# Sheet1.net
KiCad netlist of a schematic drawn in Altium Designer
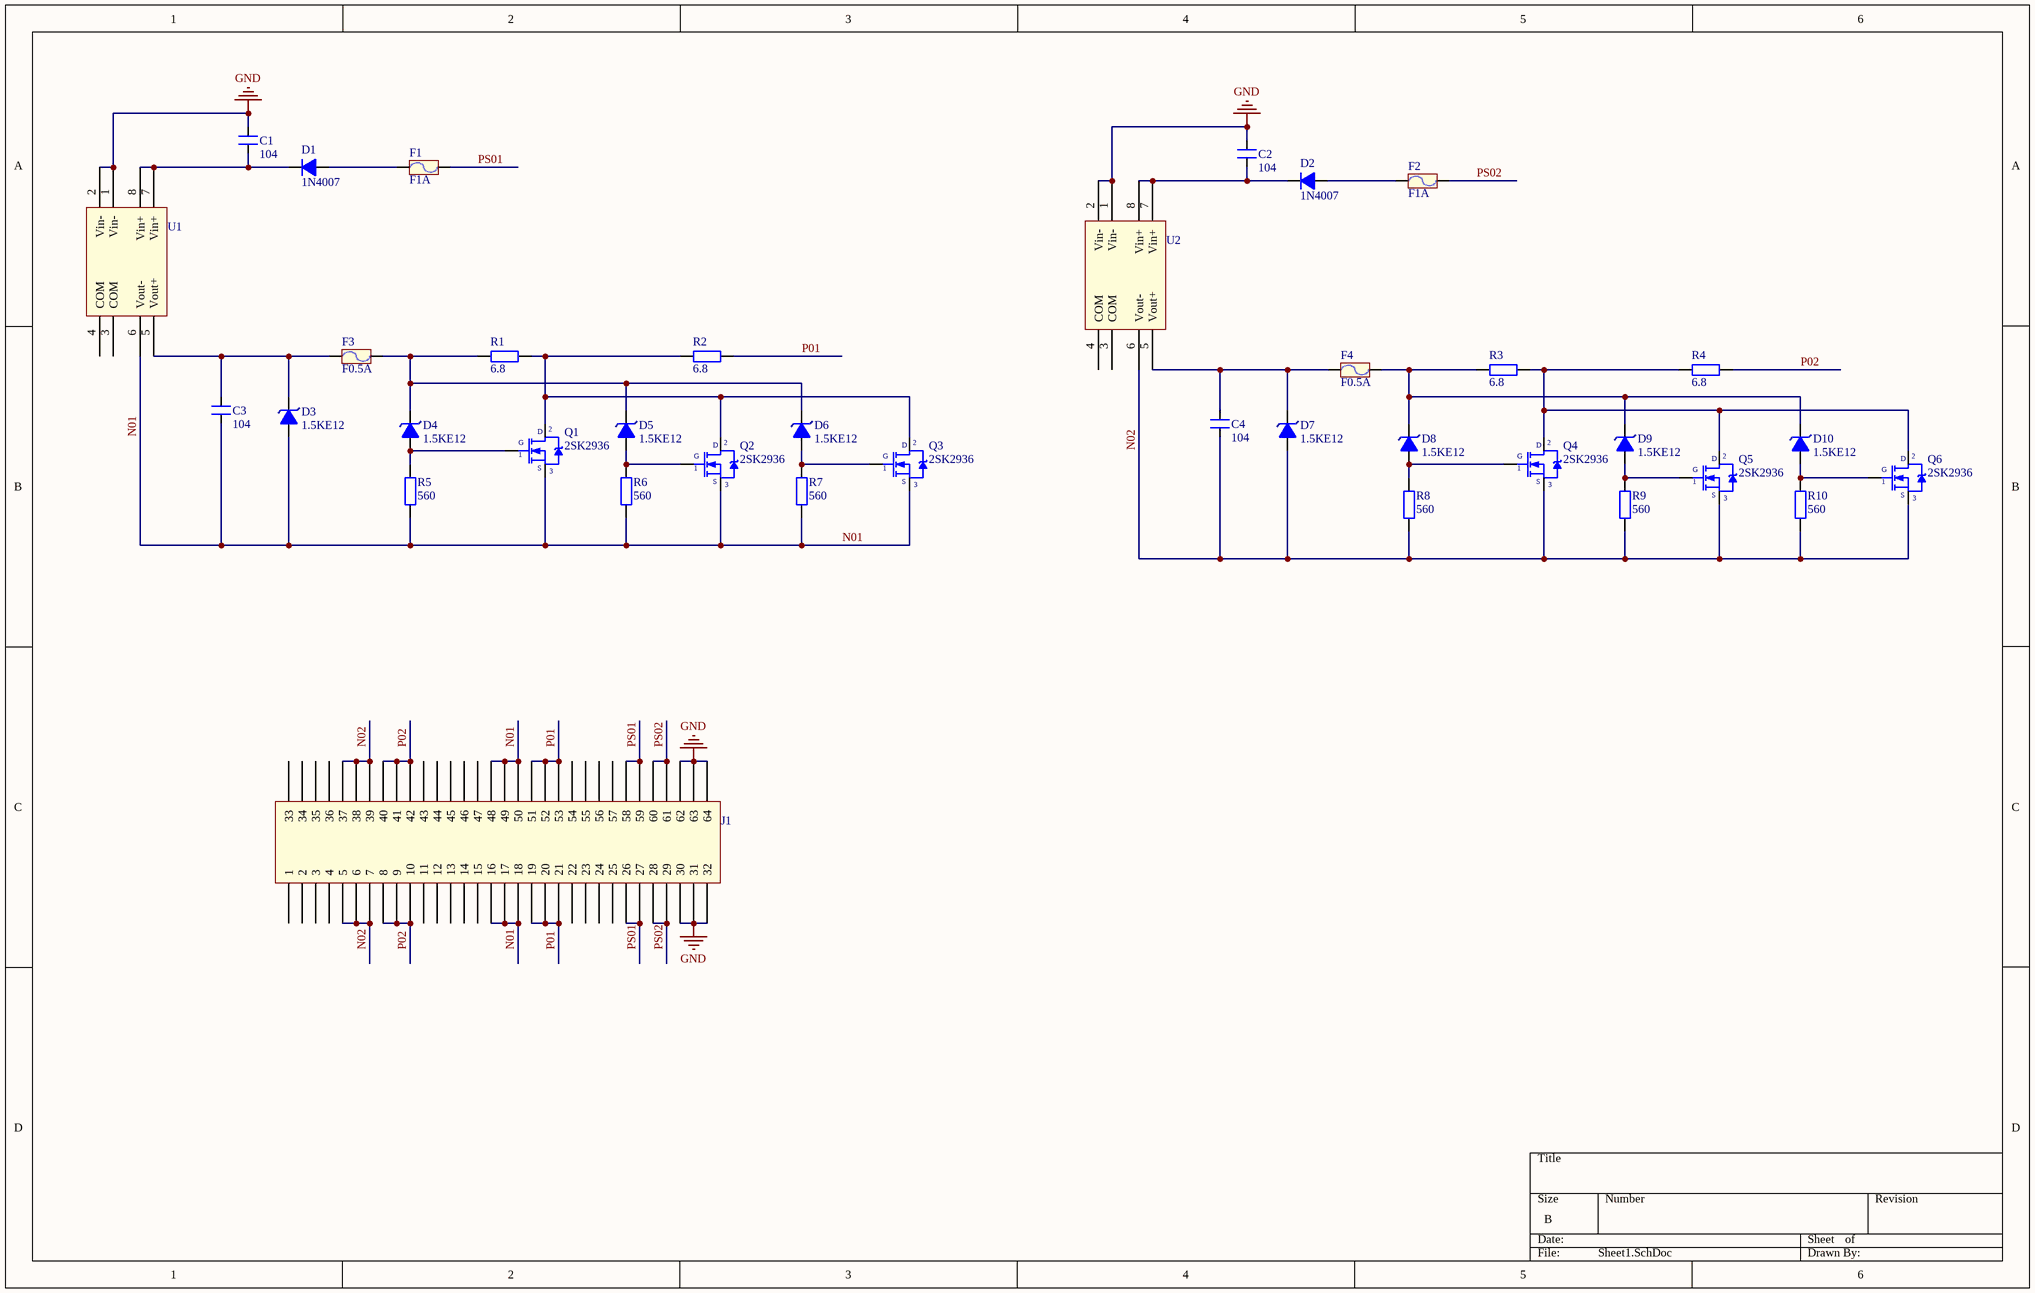
[diagram p0: Sheet1.SchDoc]

(export (version "E")
  (design (tool "Eeschema 10.0.6"))
  (components
    (comp (ref "C1")
      (value "104")
      (footprint "CN1")
      (description "Cremic For Xtal 1pF => 100pF")
      (libsource (lib "Binh_BK") (part "CAP"))
    )
    (comp (ref "C2")
      (value "104")
      (footprint "CN1")
      (description "Cremic For Xtal 1pF => 100pF")
      (libsource (lib "Binh_BK") (part "CAP"))
    )
    (comp (ref "C3")
      (value "104")
      (footprint "CN1")
      (description "Cremic For Xtal 1pF => 100pF")
      (libsource (lib "Binh_BK") (part "CAP"))
    )
    (comp (ref "C4")
      (value "104")
      (footprint "CN1")
      (description "Cremic For Xtal 1pF => 100pF")
      (libsource (lib "Binh_BK") (part "CAP"))
    )
    (comp (ref "D1")
      (value "1N4007")
      (footprint "D1A")
      (description "Diode 1A")
      (libsource (lib "Binh_BK") (part "D1A"))
    )
    (comp (ref "D2")
      (value "1N4007")
      (footprint "D1A")
      (description "Diode 1A")
      (libsource (lib "Binh_BK") (part "D1A"))
    )
    (comp (ref "D3") (value "1.5KE12") (footprint "D1A") (libsource (lib "Binh_BK") (part "Zener")))
    (comp (ref "D4") (value "1.5KE12") (footprint "D1A") (libsource (lib "Binh_BK") (part "Zener")))
    (comp (ref "D5") (value "1.5KE12") (footprint "D1A") (libsource (lib "Binh_BK") (part "Zener")))
    (comp (ref "D6") (value "1.5KE12") (footprint "D1A") (libsource (lib "Binh_BK") (part "Zener")))
    (comp (ref "D7") (value "1.5KE12") (footprint "D1A") (libsource (lib "Binh_BK") (part "Zener")))
    (comp (ref "D8") (value "1.5KE12") (footprint "D1A") (libsource (lib "Binh_BK") (part "Zener")))
    (comp (ref "D9") (value "1.5KE12") (footprint "D1A") (libsource (lib "Binh_BK") (part "Zener")))
    (comp (ref "D10") (value "1.5KE12") (footprint "D1A") (libsource (lib "Binh_BK") (part "Zener")))
    (comp (ref "F1")
      (value "F1A")
      (footprint "Fuse")
      (description "Fuse")
      (fields (field (name "DESIGNED BY") "VanDungEvn"))
      (libsource (lib "") (part "Fuse_1"))
    )
    (comp (ref "F2")
      (value "F1A")
      (footprint "Fuse")
      (description "Fuse")
      (fields (field (name "DESIGNED BY") "VanDungEvn"))
      (libsource (lib "") (part "Fuse_1"))
    )
    (comp (ref "F3")
      (value "F0.5A")
      (footprint "Fuse")
      (description "Fuse")
      (fields (field (name "DESIGNED BY") "VanDungEvn"))
      (libsource (lib "Binh_BK") (part "Fuse"))
    )
    (comp (ref "F4")
      (value "F0.5A")
      (footprint "Fuse")
      (description "Fuse")
      (fields (field (name "DESIGNED BY") "VanDungEvn"))
      (libsource (lib "Binh_BK") (part "Fuse"))
    )
    (comp (ref "J1")
      (value "Header 32x2")
      (footprint "Header32x2")
      (libsource (lib "dung_maker_2018") (part "Header 32x2"))
    )
    (comp (ref "Q1")
      (value "2SK2936")
      (footprint "QTO-220")
      (description "MOSFET N - CHANNEL 500V - 0.75 - 8A - TO-220")
      (libsource (lib "Binh_BK") (part "IRF840"))
    )
    (comp (ref "Q2")
      (value "2SK2936")
      (footprint "QTO-220")
      (description "MOSFET N - CHANNEL 500V - 0.75 - 8A - TO-220")
      (libsource (lib "Binh_BK") (part "IRF840"))
    )
    (comp (ref "Q3")
      (value "2SK2936")
      (footprint "QTO-220")
      (description "MOSFET N - CHANNEL 500V - 0.75 - 8A - TO-220")
      (libsource (lib "Binh_BK") (part "IRF840"))
    )
    (comp (ref "Q4")
      (value "2SK2936")
      (footprint "QTO-220")
      (description "MOSFET N - CHANNEL 500V - 0.75 - 8A - TO-220")
      (libsource (lib "Binh_BK") (part "IRF840"))
    )
    (comp (ref "Q5")
      (value "2SK2936")
      (footprint "QTO-220")
      (description "MOSFET N - CHANNEL 500V - 0.75 - 8A - TO-220")
      (libsource (lib "Binh_BK") (part "IRF840"))
    )
    (comp (ref "Q6")
      (value "2SK2936")
      (footprint "QTO-220")
      (description "MOSFET N - CHANNEL 500V - 0.75 - 8A - TO-220")
      (libsource (lib "Binh_BK") (part "IRF840"))
    )
    (comp (ref "R1")
      (value "6.8")
      (footprint "R5W")
      (description "Resistor 1/4W")
      (libsource (lib "Binh_BK") (part "R1/4W"))
    )
    (comp (ref "R2")
      (value "6.8")
      (footprint "R5W")
      (description "Resistor 1/4W")
      (libsource (lib "Binh_BK") (part "R1/4W"))
    )
    (comp (ref "R3")
      (value "6.8")
      (footprint "R5W")
      (description "Resistor 1/4W")
      (libsource (lib "Binh_BK") (part "R1/4W"))
    )
    (comp (ref "R4")
      (value "6.8")
      (footprint "R5W")
      (description "Resistor 1/4W")
      (libsource (lib "Binh_BK") (part "R1/4W"))
    )
    (comp (ref "R5")
      (value "560")
      (footprint "R1/4W")
      (description "Resistor 1/4W")
      (libsource (lib "Binh_BK") (part "R1/4W"))
    )
    (comp (ref "R6")
      (value "560")
      (footprint "R1/4W")
      (description "Resistor 1/4W")
      (libsource (lib "Binh_BK") (part "R1/4W"))
    )
    (comp (ref "R7")
      (value "560")
      (footprint "R1/4W")
      (description "Resistor 1/4W")
      (libsource (lib "Binh_BK") (part "R1/4W"))
    )
    (comp (ref "R8")
      (value "560")
      (footprint "R1/4W")
      (description "Resistor 1/4W")
      (libsource (lib "Binh_BK") (part "R1/4W"))
    )
    (comp (ref "R9")
      (value "560")
      (footprint "R1/4W")
      (description "Resistor 1/4W")
      (libsource (lib "Binh_BK") (part "R1/4W"))
    )
    (comp (ref "R10")
      (value "560")
      (footprint "R1/4W")
      (description "Resistor 1/4W")
      (libsource (lib "Binh_BK") (part "R1/4W"))
    )
    (comp (ref "U1") (value "ASA01xx") (footprint "ASA") (libsource (lib "dung_maker_2018") (part "ASA01")))
    (comp (ref "U2") (value "ASA01xx") (footprint "ASA") (libsource (lib "dung_maker_2018") (part "ASA01")))
  )
  (nets
    (net (code "1") (name "/N01") (class "Default")
      (node (ref "C3") (pin "1") (pinfunction "1_1") (pintype "passive"))
      (node (ref "D3") (pin "1") (pinfunction "A_1") (pintype "passive"))
      (node (ref "J1") (pin "16") (pinfunction "16_16") (pintype "passive"))
      (node (ref "J1") (pin "17") (pinfunction "17_17") (pintype "passive"))
      (node (ref "J1") (pin "18") (pinfunction "18_18") (pintype "passive"))
      (node (ref "J1") (pin "48") (pinfunction "48_48") (pintype "passive"))
      (node (ref "J1") (pin "49") (pinfunction "49_49") (pintype "passive"))
      (node (ref "J1") (pin "50") (pinfunction "50_50") (pintype "passive"))
      (node (ref "Q1") (pin "3") (pinfunction "S_3") (pintype "passive"))
      (node (ref "Q2") (pin "3") (pinfunction "S_3") (pintype "passive"))
      (node (ref "Q3") (pin "3") (pinfunction "S_3") (pintype "passive"))
      (node (ref "R5") (pin "1") (pinfunction "1_1") (pintype "passive"))
      (node (ref "R6") (pin "1") (pinfunction "1_1") (pintype "passive"))
      (node (ref "R7") (pin "1") (pinfunction "1_1") (pintype "passive"))
      (node (ref "U1") (pin "6") (pinfunction "Vout-_6") (pintype "passive"))
    )
    (net (code "2") (name "/N02") (class "Default")
      (node (ref "C4") (pin "1") (pinfunction "1_1") (pintype "passive"))
      (node (ref "D7") (pin "1") (pinfunction "A_1") (pintype "passive"))
      (node (ref "J1") (pin "37") (pinfunction "37_37") (pintype "passive"))
      (node (ref "J1") (pin "38") (pinfunction "38_38") (pintype "passive"))
      (node (ref "J1") (pin "39") (pinfunction "39_39") (pintype "passive"))
      (node (ref "J1") (pin "5") (pinfunction "5_5") (pintype "passive"))
      (node (ref "J1") (pin "6") (pinfunction "6_6") (pintype "passive"))
      (node (ref "J1") (pin "7") (pinfunction "7_7") (pintype "passive"))
      (node (ref "Q4") (pin "3") (pinfunction "S_3") (pintype "passive"))
      (node (ref "Q5") (pin "3") (pinfunction "S_3") (pintype "passive"))
      (node (ref "Q6") (pin "3") (pinfunction "S_3") (pintype "passive"))
      (node (ref "R10") (pin "1") (pinfunction "1_1") (pintype "passive"))
      (node (ref "R8") (pin "1") (pinfunction "1_1") (pintype "passive"))
      (node (ref "R9") (pin "1") (pinfunction "1_1") (pintype "passive"))
      (node (ref "U2") (pin "6") (pinfunction "Vout-_6") (pintype "passive"))
    )
    (net (code "3") (name "/P01") (class "Default")
      (node (ref "J1") (pin "19") (pinfunction "19_19") (pintype "passive"))
      (node (ref "J1") (pin "20") (pinfunction "20_20") (pintype "passive"))
      (node (ref "J1") (pin "21") (pinfunction "21_21") (pintype "passive"))
      (node (ref "J1") (pin "51") (pinfunction "51_51") (pintype "passive"))
      (node (ref "J1") (pin "52") (pinfunction "52_52") (pintype "passive"))
      (node (ref "J1") (pin "53") (pinfunction "53_53") (pintype "passive"))
      (node (ref "R2") (pin "1") (pinfunction "1_1") (pintype "passive"))
    )
    (net (code "4") (name "/P02") (class "Default")
      (node (ref "J1") (pin "10") (pinfunction "10_10") (pintype "passive"))
      (node (ref "J1") (pin "40") (pinfunction "40_40") (pintype "passive"))
      (node (ref "J1") (pin "41") (pinfunction "41_41") (pintype "passive"))
      (node (ref "J1") (pin "42") (pinfunction "42_42") (pintype "passive"))
      (node (ref "J1") (pin "8") (pinfunction "8_8") (pintype "passive"))
      (node (ref "J1") (pin "9") (pinfunction "9_9") (pintype "passive"))
      (node (ref "R4") (pin "1") (pinfunction "1_1") (pintype "passive"))
    )
    (net (code "5") (name "/PS01") (class "Default")
      (node (ref "F1") (pin "2") (pinfunction "2_2") (pintype "passive"))
      (node (ref "J1") (pin "26") (pinfunction "26_26") (pintype "passive"))
      (node (ref "J1") (pin "27") (pinfunction "27_27") (pintype "passive"))
      (node (ref "J1") (pin "58") (pinfunction "58_58") (pintype "passive"))
      (node (ref "J1") (pin "59") (pinfunction "59_59") (pintype "passive"))
    )
    (net (code "6") (name "/PS02") (class "Default")
      (node (ref "F2") (pin "2") (pinfunction "2_2") (pintype "passive"))
      (node (ref "J1") (pin "28") (pinfunction "28_28") (pintype "passive"))
      (node (ref "J1") (pin "29") (pinfunction "29_29") (pintype "passive"))
      (node (ref "J1") (pin "60") (pinfunction "60_60") (pintype "passive"))
      (node (ref "J1") (pin "61") (pinfunction "61_61") (pintype "passive"))
    )
    (net (code "7") (name "GND") (class "Default")
      (node (ref "C1") (pin "2") (pinfunction "2_2") (pintype "passive"))
      (node (ref "C2") (pin "2") (pinfunction "2_2") (pintype "passive"))
      (node (ref "J1") (pin "30") (pinfunction "30_30") (pintype "passive"))
      (node (ref "J1") (pin "31") (pinfunction "31_31") (pintype "passive"))
      (node (ref "J1") (pin "32") (pinfunction "32_32") (pintype "passive"))
      (node (ref "J1") (pin "62") (pinfunction "62_62") (pintype "passive"))
      (node (ref "J1") (pin "63") (pinfunction "63_63") (pintype "passive"))
      (node (ref "J1") (pin "64") (pinfunction "64_64") (pintype "passive"))
      (node (ref "U1") (pin "1") (pinfunction "Vin-_1") (pintype "passive"))
      (node (ref "U1") (pin "2") (pinfunction "Vin-_2") (pintype "passive"))
      (node (ref "U2") (pin "1") (pinfunction "Vin-_1") (pintype "passive"))
      (node (ref "U2") (pin "2") (pinfunction "Vin-_2") (pintype "passive"))
    )
    (net (code "8") (name "Net-(D1-A)") (class "Default")
      (node (ref "D1") (pin "1") (pinfunction "A_1") (pintype "passive"))
      (node (ref "F1") (pin "1") (pinfunction "1_1") (pintype "passive"))
    )
    (net (code "9") (name "Net-(D1-K)") (class "Default")
      (node (ref "C1") (pin "1") (pinfunction "1_1") (pintype "passive"))
      (node (ref "D1") (pin "2") (pinfunction "K_2") (pintype "passive"))
      (node (ref "U1") (pin "7") (pinfunction "Vin+_7") (pintype "passive"))
      (node (ref "U1") (pin "8") (pinfunction "Vin+_8") (pintype "passive"))
    )
    (net (code "10") (name "Net-(D2-A)") (class "Default")
      (node (ref "D2") (pin "1") (pinfunction "A_1") (pintype "passive"))
      (node (ref "F2") (pin "1") (pinfunction "1_1") (pintype "passive"))
    )
    (net (code "11") (name "Net-(D2-K)") (class "Default")
      (node (ref "C2") (pin "1") (pinfunction "1_1") (pintype "passive"))
      (node (ref "D2") (pin "2") (pinfunction "K_2") (pintype "passive"))
      (node (ref "U2") (pin "7") (pinfunction "Vin+_7") (pintype "passive"))
      (node (ref "U2") (pin "8") (pinfunction "Vin+_8") (pintype "passive"))
    )
    (net (code "12") (name "Net-(D3-K)") (class "Default")
      (node (ref "C3") (pin "2") (pinfunction "2_2") (pintype "passive"))
      (node (ref "D3") (pin "2") (pinfunction "K_2") (pintype "passive"))
      (node (ref "F3") (pin "2") (pinfunction "2_2") (pintype "passive"))
      (node (ref "U1") (pin "5") (pinfunction "Vout+_5") (pintype "passive"))
    )
    (net (code "13") (name "Net-(D4-A)") (class "Default")
      (node (ref "D4") (pin "1") (pinfunction "A_1") (pintype "passive"))
      (node (ref "Q1") (pin "1") (pinfunction "G_1") (pintype "passive"))
      (node (ref "R5") (pin "2") (pinfunction "2_2") (pintype "passive"))
    )
    (net (code "14") (name "Net-(D4-K)") (class "Default")
      (node (ref "D4") (pin "2") (pinfunction "K_2") (pintype "passive"))
      (node (ref "D5") (pin "2") (pinfunction "K_2") (pintype "passive"))
      (node (ref "D6") (pin "2") (pinfunction "K_2") (pintype "passive"))
      (node (ref "F3") (pin "1") (pinfunction "1_1") (pintype "passive"))
      (node (ref "R1") (pin "2") (pinfunction "2_2") (pintype "passive"))
    )
    (net (code "15") (name "Net-(D5-A)") (class "Default")
      (node (ref "D5") (pin "1") (pinfunction "A_1") (pintype "passive"))
      (node (ref "Q2") (pin "1") (pinfunction "G_1") (pintype "passive"))
      (node (ref "R6") (pin "2") (pinfunction "2_2") (pintype "passive"))
    )
    (net (code "16") (name "Net-(D6-A)") (class "Default")
      (node (ref "D6") (pin "1") (pinfunction "A_1") (pintype "passive"))
      (node (ref "Q3") (pin "1") (pinfunction "G_1") (pintype "passive"))
      (node (ref "R7") (pin "2") (pinfunction "2_2") (pintype "passive"))
    )
    (net (code "17") (name "Net-(D7-K)") (class "Default")
      (node (ref "C4") (pin "2") (pinfunction "2_2") (pintype "passive"))
      (node (ref "D7") (pin "2") (pinfunction "K_2") (pintype "passive"))
      (node (ref "F4") (pin "2") (pinfunction "2_2") (pintype "passive"))
      (node (ref "U2") (pin "5") (pinfunction "Vout+_5") (pintype "passive"))
    )
    (net (code "18") (name "Net-(D8-A)") (class "Default")
      (node (ref "D8") (pin "1") (pinfunction "A_1") (pintype "passive"))
      (node (ref "Q4") (pin "1") (pinfunction "G_1") (pintype "passive"))
      (node (ref "R8") (pin "2") (pinfunction "2_2") (pintype "passive"))
    )
    (net (code "19") (name "Net-(D9-A)") (class "Default")
      (node (ref "D9") (pin "1") (pinfunction "A_1") (pintype "passive"))
      (node (ref "Q5") (pin "1") (pinfunction "G_1") (pintype "passive"))
      (node (ref "R9") (pin "2") (pinfunction "2_2") (pintype "passive"))
    )
    (net (code "20") (name "Net-(D10-A)") (class "Default")
      (node (ref "D10") (pin "1") (pinfunction "A_1") (pintype "passive"))
      (node (ref "Q6") (pin "1") (pinfunction "G_1") (pintype "passive"))
      (node (ref "R10") (pin "2") (pinfunction "2_2") (pintype "passive"))
    )
    (net (code "21") (name "Net-(D10-K)") (class "Default")
      (node (ref "D10") (pin "2") (pinfunction "K_2") (pintype "passive"))
      (node (ref "D8") (pin "2") (pinfunction "K_2") (pintype "passive"))
      (node (ref "D9") (pin "2") (pinfunction "K_2") (pintype "passive"))
      (node (ref "F4") (pin "1") (pinfunction "1_1") (pintype "passive"))
      (node (ref "R3") (pin "2") (pinfunction "2_2") (pintype "passive"))
    )
    (net (code "22") (name "Net-(Q1-D)") (class "Default")
      (node (ref "Q1") (pin "2") (pinfunction "D_2") (pintype "passive"))
      (node (ref "Q2") (pin "2") (pinfunction "D_2") (pintype "passive"))
      (node (ref "Q3") (pin "2") (pinfunction "D_2") (pintype "passive"))
      (node (ref "R1") (pin "1") (pinfunction "1_1") (pintype "passive"))
      (node (ref "R2") (pin "2") (pinfunction "2_2") (pintype "passive"))
    )
    (net (code "23") (name "Net-(Q4-D)") (class "Default")
      (node (ref "Q4") (pin "2") (pinfunction "D_2") (pintype "passive"))
      (node (ref "Q5") (pin "2") (pinfunction "D_2") (pintype "passive"))
      (node (ref "Q6") (pin "2") (pinfunction "D_2") (pintype "passive"))
      (node (ref "R3") (pin "1") (pinfunction "1_1") (pintype "passive"))
      (node (ref "R4") (pin "2") (pinfunction "2_2") (pintype "passive"))
    )
    (net (code "24") (name "unconnected-(J1-Pad1)") (class "Default")
      (node (ref "J1") (pin "1") (pinfunction "1_1") (pintype "passive"))
    )
    (net (code "25") (name "unconnected-(J1-Pad2)") (class "Default")
      (node (ref "J1") (pin "2") (pinfunction "2_2") (pintype "passive"))
    )
    (net (code "26") (name "unconnected-(J1-Pad3)") (class "Default")
      (node (ref "J1") (pin "3") (pinfunction "3_3") (pintype "passive"))
    )
    (net (code "27") (name "unconnected-(J1-Pad4)") (class "Default")
      (node (ref "J1") (pin "4") (pinfunction "4_4") (pintype "passive"))
    )
    (net (code "28") (name "unconnected-(J1-Pad11)") (class "Default")
      (node (ref "J1") (pin "11") (pinfunction "11_11") (pintype "passive"))
    )
    (net (code "29") (name "unconnected-(J1-Pad12)") (class "Default")
      (node (ref "J1") (pin "12") (pinfunction "12_12") (pintype "passive"))
    )
    (net (code "30") (name "unconnected-(J1-Pad13)") (class "Default")
      (node (ref "J1") (pin "13") (pinfunction "13_13") (pintype "passive"))
    )
    (net (code "31") (name "unconnected-(J1-Pad14)") (class "Default")
      (node (ref "J1") (pin "14") (pinfunction "14_14") (pintype "passive"))
    )
    (net (code "32") (name "unconnected-(J1-Pad15)") (class "Default")
      (node (ref "J1") (pin "15") (pinfunction "15_15") (pintype "passive"))
    )
    (net (code "33") (name "unconnected-(J1-Pad22)") (class "Default")
      (node (ref "J1") (pin "22") (pinfunction "22_22") (pintype "passive"))
    )
    (net (code "34") (name "unconnected-(J1-Pad23)") (class "Default")
      (node (ref "J1") (pin "23") (pinfunction "23_23") (pintype "passive"))
    )
    (net (code "35") (name "unconnected-(J1-Pad24)") (class "Default")
      (node (ref "J1") (pin "24") (pinfunction "24_24") (pintype "passive"))
    )
    (net (code "36") (name "unconnected-(J1-Pad25)") (class "Default")
      (node (ref "J1") (pin "25") (pinfunction "25_25") (pintype "passive"))
    )
    (net (code "37") (name "unconnected-(J1-Pad33)") (class "Default")
      (node (ref "J1") (pin "33") (pinfunction "33_33") (pintype "passive"))
    )
    (net (code "38") (name "unconnected-(J1-Pad34)") (class "Default")
      (node (ref "J1") (pin "34") (pinfunction "34_34") (pintype "passive"))
    )
    (net (code "39") (name "unconnected-(J1-Pad35)") (class "Default")
      (node (ref "J1") (pin "35") (pinfunction "35_35") (pintype "passive"))
    )
    (net (code "40") (name "unconnected-(J1-Pad36)") (class "Default")
      (node (ref "J1") (pin "36") (pinfunction "36_36") (pintype "passive"))
    )
    (net (code "41") (name "unconnected-(J1-Pad43)") (class "Default")
      (node (ref "J1") (pin "43") (pinfunction "43_43") (pintype "passive"))
    )
    (net (code "42") (name "unconnected-(J1-Pad44)") (class "Default")
      (node (ref "J1") (pin "44") (pinfunction "44_44") (pintype "passive"))
    )
    (net (code "43") (name "unconnected-(J1-Pad45)") (class "Default")
      (node (ref "J1") (pin "45") (pinfunction "45_45") (pintype "passive"))
    )
    (net (code "44") (name "unconnected-(J1-Pad46)") (class "Default")
      (node (ref "J1") (pin "46") (pinfunction "46_46") (pintype "passive"))
    )
    (net (code "45") (name "unconnected-(J1-Pad47)") (class "Default")
      (node (ref "J1") (pin "47") (pinfunction "47_47") (pintype "passive"))
    )
    (net (code "46") (name "unconnected-(J1-Pad54)") (class "Default")
      (node (ref "J1") (pin "54") (pinfunction "54_54") (pintype "passive"))
    )
    (net (code "47") (name "unconnected-(J1-Pad55)") (class "Default")
      (node (ref "J1") (pin "55") (pinfunction "55_55") (pintype "passive"))
    )
    (net (code "48") (name "unconnected-(J1-Pad56)") (class "Default")
      (node (ref "J1") (pin "56") (pinfunction "56_56") (pintype "passive"))
    )
    (net (code "49") (name "unconnected-(J1-Pad57)") (class "Default")
      (node (ref "J1") (pin "57") (pinfunction "57_57") (pintype "passive"))
    )
    (net (code "50") (name "unconnected-(U1-COM-Pad3)") (class "Default")
      (node (ref "U1") (pin "3") (pinfunction "COM_3") (pintype "passive"))
    )
    (net (code "51") (name "unconnected-(U1-COM-Pad4)") (class "Default")
      (node (ref "U1") (pin "4") (pinfunction "COM_4") (pintype "passive"))
    )
    (net (code "52") (name "unconnected-(U2-COM-Pad3)") (class "Default")
      (node (ref "U2") (pin "3") (pinfunction "COM_3") (pintype "passive"))
    )
    (net (code "53") (name "unconnected-(U2-COM-Pad4)") (class "Default")
      (node (ref "U2") (pin "4") (pinfunction "COM_4") (pintype "passive"))
    )
  )
)
